# quadcopter-smith.net
KiCad netlist of a schematic drawn in EAGLE
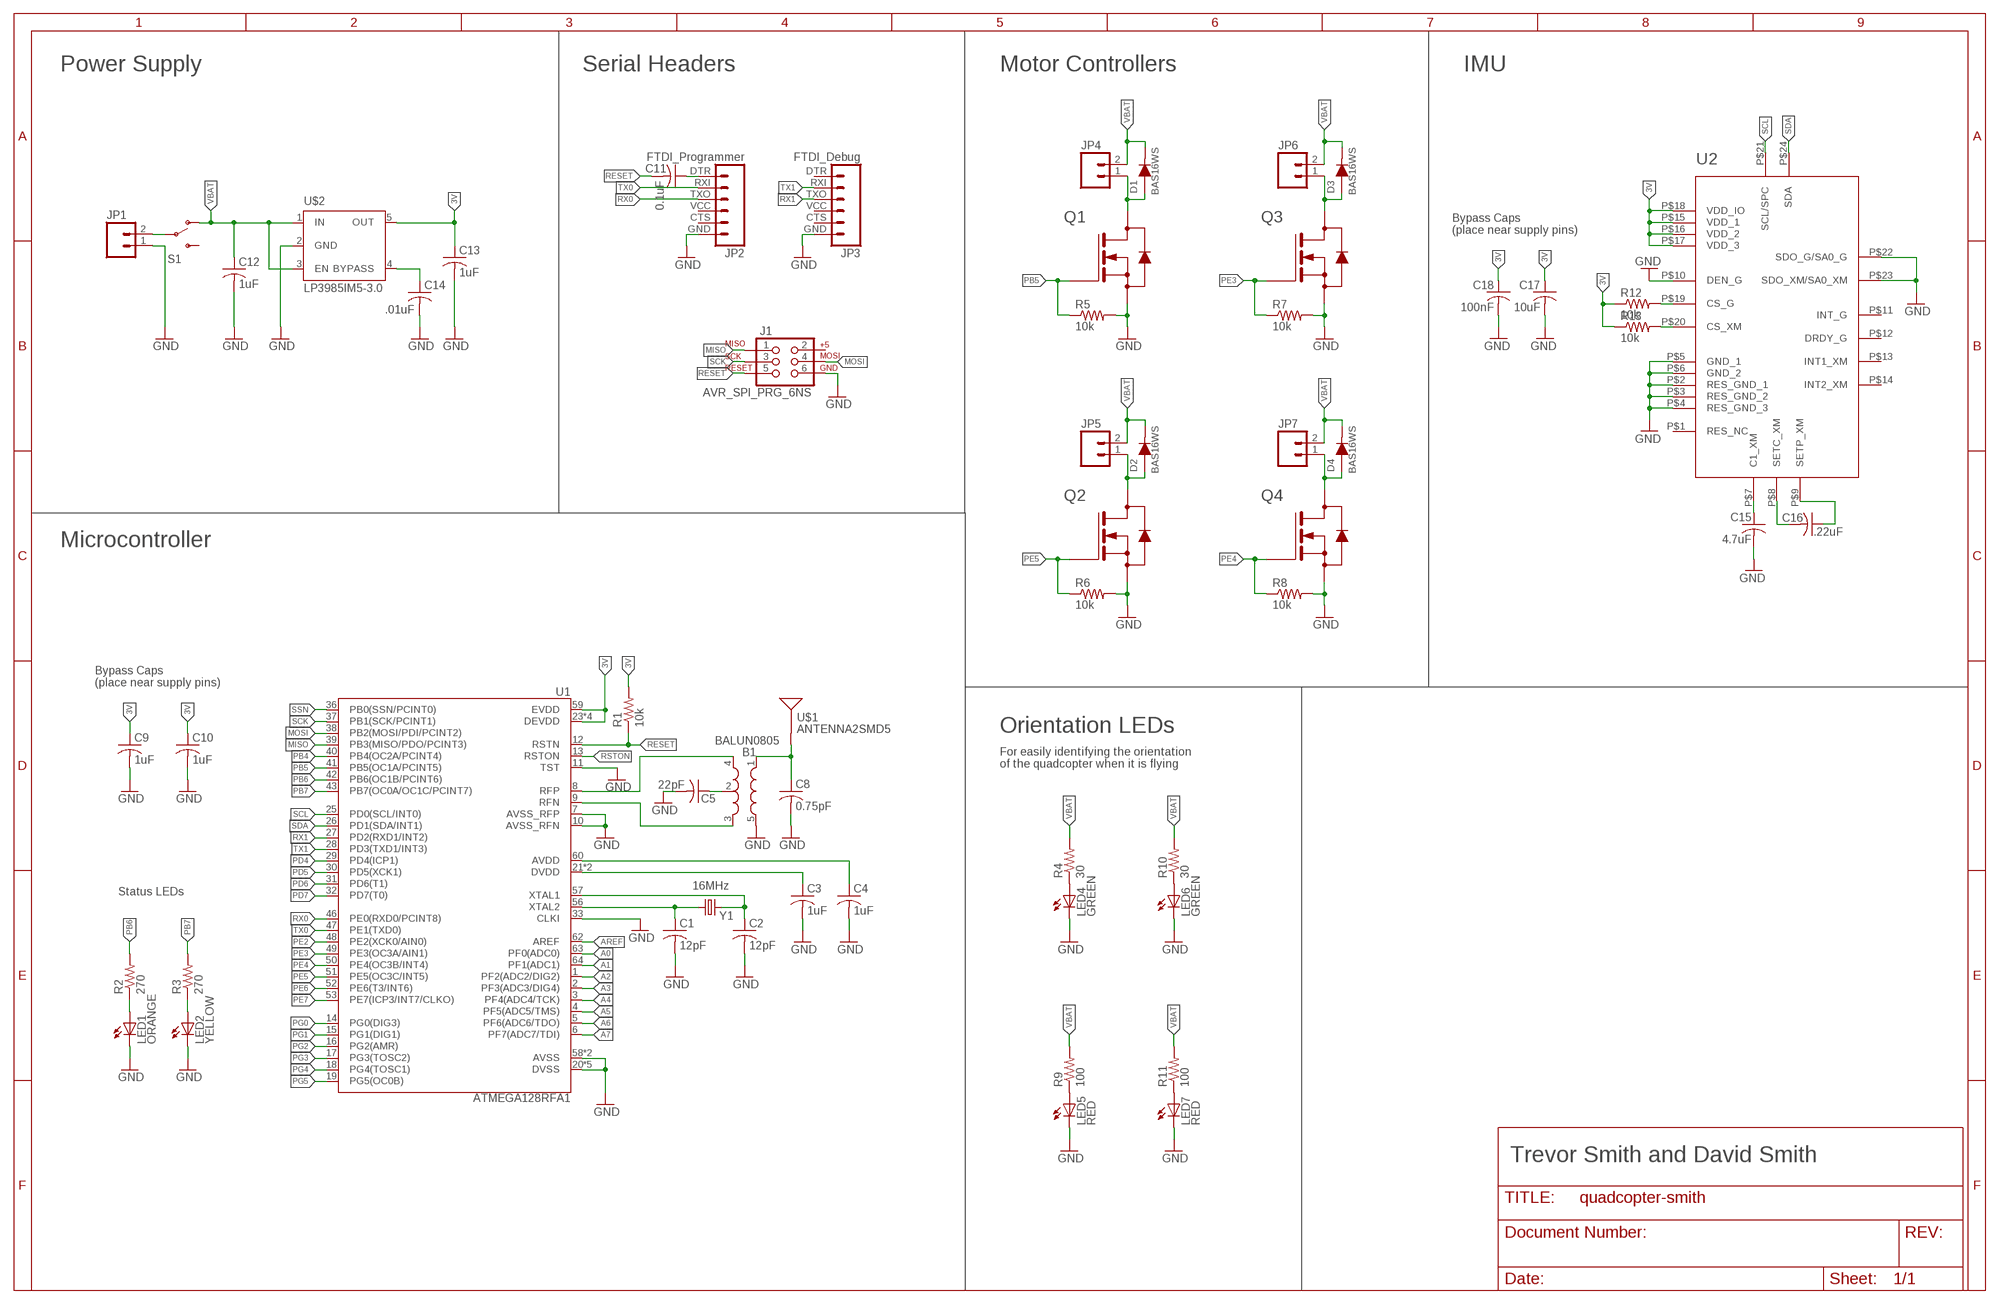
[diagram p0: schematic, sheet 1]

(export (version "E")
  (design (tool "Eeschema 10.0.6"))
  (components
    (comp (ref "B1")
      (value "BALUN0805")
      (footprint "eagle-import:BALUN")
      (libsource (lib "eagle-import") (part "BALUN0805"))
    )
    (comp (ref "C1")
      (value "12pF")
      (footprint "eagle-import:C0805")
      (libsource (lib "eagle-import") (part "C-USC0805"))
    )
    (comp (ref "C2")
      (value "12pF")
      (footprint "eagle-import:C0805")
      (libsource (lib "eagle-import") (part "C-USC0805"))
    )
    (comp (ref "C3")
      (value "1uF")
      (footprint "eagle-import:C0805")
      (libsource (lib "eagle-import") (part "C-USC0805"))
    )
    (comp (ref "C4")
      (value "1uF")
      (footprint "eagle-import:C0805")
      (libsource (lib "eagle-import") (part "C-USC0805"))
    )
    (comp (ref "C5")
      (value "22pF")
      (footprint "eagle-import:C0805")
      (libsource (lib "eagle-import") (part "C-USC0805"))
    )
    (comp (ref "C8")
      (value "0.75pF")
      (footprint "eagle-import:C0805")
      (libsource (lib "eagle-import") (part "C-USC0805"))
    )
    (comp (ref "C9")
      (value "1uF")
      (footprint "eagle-import:C0805")
      (libsource (lib "eagle-import") (part "C-USC0805"))
    )
    (comp (ref "C10")
      (value "1uF")
      (footprint "eagle-import:C0805")
      (libsource (lib "eagle-import") (part "C-USC0805"))
    )
    (comp (ref "C11")
      (value "0.1uF")
      (footprint "eagle-import:C0805")
      (libsource (lib "eagle-import") (part "C-USC0805"))
    )
    (comp (ref "C12")
      (value "1uF")
      (footprint "eagle-import:C0805")
      (libsource (lib "eagle-import") (part "C-USC0805"))
    )
    (comp (ref "C13")
      (value "1uF")
      (footprint "eagle-import:C0805")
      (libsource (lib "eagle-import") (part "C-USC0805"))
    )
    (comp (ref "C14")
      (value ".01uF")
      (footprint "eagle-import:C0805")
      (libsource (lib "eagle-import") (part "C-USC0805"))
    )
    (comp (ref "C15")
      (value "4.7uF")
      (footprint "eagle-import:C0805")
      (libsource (lib "eagle-import") (part "C-USC0805"))
    )
    (comp (ref "C16")
      (value ".22uF")
      (footprint "eagle-import:C0805")
      (libsource (lib "eagle-import") (part "C-USC0805"))
    )
    (comp (ref "C17")
      (value "10uF")
      (footprint "eagle-import:C0805")
      (libsource (lib "eagle-import") (part "C-USC0805"))
    )
    (comp (ref "C18")
      (value "100nF")
      (footprint "eagle-import:C0805")
      (libsource (lib "eagle-import") (part "C-USC0805"))
    )
    (comp (ref "D1")
      (value "BAS16WS")
      (footprint "eagle-import:SOD-323")
      (fields (field (name "CREATOR") "Trevor Smith"))
      (libsource (lib "eagle-import") (part "BAS16WS"))
    )
    (comp (ref "D2")
      (value "BAS16WS")
      (footprint "eagle-import:SOD-323")
      (fields (field (name "CREATOR") "Trevor Smith"))
      (libsource (lib "eagle-import") (part "BAS16WS"))
    )
    (comp (ref "D3")
      (value "BAS16WS")
      (footprint "eagle-import:SOD-323")
      (fields (field (name "CREATOR") "Trevor Smith"))
      (libsource (lib "eagle-import") (part "BAS16WS"))
    )
    (comp (ref "D4")
      (value "BAS16WS")
      (footprint "eagle-import:SOD-323")
      (fields (field (name "CREATOR") "Trevor Smith"))
      (libsource (lib "eagle-import") (part "BAS16WS"))
    )
    (comp (ref "J1")
      (value "AVR_SPI_PRG_6NS")
      (footprint "eagle-import:2X3-NS")
      (libsource (lib "eagle-import") (part "AVR_SPI_PRG_6NS"))
    )
    (comp (ref "JP1")
      (value "M02PTH")
      (footprint "eagle-import:1X02")
      (libsource (lib "eagle-import") (part "M02PTH"))
    )
    (comp (ref "JP2")
      (value "FTDI_Programmer")
      (footprint "eagle-import:FTDI_BASIC")
      (libsource (lib "eagle-import") (part "FTDI_BASICPTH"))
    )
    (comp (ref "JP3")
      (value "FTDI_Debug")
      (footprint "eagle-import:FTDI_BASIC")
      (libsource (lib "eagle-import") (part "FTDI_BASICPTH"))
    )
    (comp (ref "JP4")
      (value "M02PTH")
      (footprint "eagle-import:1X02")
      (libsource (lib "eagle-import") (part "M02PTH"))
    )
    (comp (ref "JP5")
      (value "M02PTH")
      (footprint "eagle-import:1X02")
      (libsource (lib "eagle-import") (part "M02PTH"))
    )
    (comp (ref "JP6")
      (value "M02PTH")
      (footprint "eagle-import:1X02")
      (libsource (lib "eagle-import") (part "M02PTH"))
    )
    (comp (ref "JP7")
      (value "M02PTH")
      (footprint "eagle-import:1X02")
      (libsource (lib "eagle-import") (part "M02PTH"))
    )
    (comp (ref "LED1")
      (value "ORANGE")
      (footprint "eagle-import:CHIP-LED0805")
      (libsource (lib "eagle-import") (part "LEDCHIP-LED0805"))
    )
    (comp (ref "LED2")
      (value "YELLOW")
      (footprint "eagle-import:CHIP-LED0805")
      (libsource (lib "eagle-import") (part "LEDCHIP-LED0805"))
    )
    (comp (ref "LED4")
      (value "GREEN")
      (footprint "eagle-import:CHIP-LED0805")
      (libsource (lib "eagle-import") (part "LEDCHIP-LED0805"))
    )
    (comp (ref "LED5")
      (value "RED")
      (footprint "eagle-import:CHIP-LED0805")
      (libsource (lib "eagle-import") (part "LEDCHIP-LED0805"))
    )
    (comp (ref "LED6")
      (value "GREEN")
      (footprint "eagle-import:CHIP-LED0805")
      (libsource (lib "eagle-import") (part "LEDCHIP-LED0805"))
    )
    (comp (ref "LED7")
      (value "RED")
      (footprint "eagle-import:CHIP-LED0805")
      (libsource (lib "eagle-import") (part "LEDCHIP-LED0805"))
    )
    (comp (ref "Q1")
      (value "SI2302CDS")
      (footprint "eagle-import:SOT-23")
      (fields (field (name "CREATOR") "Trevor Smith"))
      (libsource (lib "eagle-import") (part "SI2302CDS"))
    )
    (comp (ref "Q2")
      (value "SI2302CDS")
      (footprint "eagle-import:SOT-23")
      (fields (field (name "CREATOR") "Trevor Smith"))
      (libsource (lib "eagle-import") (part "SI2302CDS"))
    )
    (comp (ref "Q3")
      (value "SI2302CDS")
      (footprint "eagle-import:SOT-23")
      (fields (field (name "CREATOR") "Trevor Smith"))
      (libsource (lib "eagle-import") (part "SI2302CDS"))
    )
    (comp (ref "Q4")
      (value "SI2302CDS")
      (footprint "eagle-import:SOT-23")
      (fields (field (name "CREATOR") "Trevor Smith"))
      (libsource (lib "eagle-import") (part "SI2302CDS"))
    )
    (comp (ref "R1")
      (value "10k")
      (footprint "eagle-import:R0805")
      (libsource (lib "eagle-import") (part "R-US_R0805"))
    )
    (comp (ref "R2")
      (value "270")
      (footprint "eagle-import:R0805")
      (libsource (lib "eagle-import") (part "R-US_R0805"))
    )
    (comp (ref "R3")
      (value "270")
      (footprint "eagle-import:R0805")
      (libsource (lib "eagle-import") (part "R-US_R0805"))
    )
    (comp (ref "R4")
      (value "30")
      (footprint "eagle-import:R0805")
      (libsource (lib "eagle-import") (part "R-US_R0805"))
    )
    (comp (ref "R5")
      (value "10k")
      (footprint "eagle-import:R0805")
      (libsource (lib "eagle-import") (part "R-US_R0805"))
    )
    (comp (ref "R6")
      (value "10k")
      (footprint "eagle-import:R0805")
      (libsource (lib "eagle-import") (part "R-US_R0805"))
    )
    (comp (ref "R7")
      (value "10k")
      (footprint "eagle-import:R0805")
      (libsource (lib "eagle-import") (part "R-US_R0805"))
    )
    (comp (ref "R8")
      (value "10k")
      (footprint "eagle-import:R0805")
      (libsource (lib "eagle-import") (part "R-US_R0805"))
    )
    (comp (ref "R9")
      (value "100")
      (footprint "eagle-import:R0805")
      (libsource (lib "eagle-import") (part "R-US_R0805"))
    )
    (comp (ref "R10")
      (value "30")
      (footprint "eagle-import:R0805")
      (libsource (lib "eagle-import") (part "R-US_R0805"))
    )
    (comp (ref "R11")
      (value "100")
      (footprint "eagle-import:R0805")
      (libsource (lib "eagle-import") (part "R-US_R0805"))
    )
    (comp (ref "R12")
      (value "10k")
      (footprint "eagle-import:R0805")
      (libsource (lib "eagle-import") (part "R-US_R0805"))
    )
    (comp (ref "R13")
      (value "10k")
      (footprint "eagle-import:R0805")
      (libsource (lib "eagle-import") (part "R-US_R0805"))
    )
    (comp (ref "S1")
      (value "SWITCH-SPDTPTH")
      (footprint "eagle-import:SWITCH-SPDT")
      (libsource (lib "eagle-import") (part "SWITCH-SPDTPTH"))
    )
    (comp (ref "U$1")
      (value "ANTENNA2SMD5")
      (footprint "eagle-import:ANTENNA-CHIP5")
      (libsource (lib "eagle-import") (part "ANTENNA2SMD5"))
    )
    (comp (ref "U$2")
      (value "LP3985IM5-3.0")
      (footprint "eagle-import:SOT23-DBV")
      (libsource (lib "eagle-import") (part "LP3985IM5-3.0"))
    )
    (comp (ref "U1")
      (value "ATMEGA128RFA1")
      (footprint "eagle-import:QFN-64")
      (libsource (lib "eagle-import") (part "ATMEGA128RFA1"))
    )
    (comp (ref "U2")
      (value "LSM9DS0-LGA24")
      (footprint "eagle-import:LGA-24")
      (fields (field (name "CREATOR") "Trevor Smith"))
      (libsource (lib "eagle-import") (part "LSM9DS0-LGA24"))
    )
    (comp (ref "Y1")
      (value "16MHz")
      (footprint "eagle-import:CRYSTAL-SMD-5X3")
      (libsource (lib "eagle-import") (part "CRYSTAL5X3"))
    )
  )
  (nets
    (net (code "1") (name "3V") (class "Default")
      (node (ref "C10") (pin "1") (pinfunction "1_1") (pintype "passive"))
      (node (ref "C13") (pin "1") (pinfunction "1_1") (pintype "passive"))
      (node (ref "C17") (pin "1") (pinfunction "1_1") (pintype "passive"))
      (node (ref "C18") (pin "1") (pinfunction "1_1") (pintype "passive"))
      (node (ref "C9") (pin "1") (pinfunction "1_1") (pintype "passive"))
      (node (ref "R1") (pin "2") (pinfunction "2_2") (pintype "passive"))
      (node (ref "R12") (pin "1") (pinfunction "1_1") (pintype "passive"))
      (node (ref "R13") (pin "1") (pinfunction "1_1") (pintype "passive"))
      (node (ref "U$2") (pin "5") (pinfunction "OUT_5") (pintype "passive"))
      (node (ref "U1") (pin "23") (pinfunction "DEVDD_23") (pintype "bidirectional"))
      (node (ref "U1") (pin "34") (pinfunction "DEVDD_34") (pintype "bidirectional"))
      (node (ref "U1") (pin "44") (pinfunction "DEVDD_44") (pintype "bidirectional"))
      (node (ref "U1") (pin "54") (pinfunction "DEVDD_54") (pintype "bidirectional"))
      (node (ref "U1") (pin "59") (pinfunction "EVDD_59") (pintype "bidirectional"))
      (node (ref "U2") (pin "P$15") (pinfunction "VDD_1_P$15") (pintype "power_in"))
      (node (ref "U2") (pin "P$16") (pinfunction "VDD_2_P$16") (pintype "power_in"))
      (node (ref "U2") (pin "P$17") (pinfunction "VDD_3_P$17") (pintype "power_in"))
      (node (ref "U2") (pin "P$18") (pinfunction "VDD_IO_P$18") (pintype "power_in"))
    )
    (net (code "2") (name "A0") (class "Default")
      (node (ref "U1") (pin "63") (pinfunction "PF0(ADC0)_63") (pintype "bidirectional"))
    )
    (net (code "3") (name "A1") (class "Default")
      (node (ref "U1") (pin "64") (pinfunction "PF1(ADC1)_64") (pintype "bidirectional"))
    )
    (net (code "4") (name "A2") (class "Default")
      (node (ref "U1") (pin "1") (pinfunction "PF2(ADC2/DIG2)_1") (pintype "bidirectional"))
    )
    (net (code "5") (name "A3") (class "Default")
      (node (ref "U1") (pin "2") (pinfunction "PF3(ADC3/DIG4)_2") (pintype "bidirectional"))
    )
    (net (code "6") (name "A4") (class "Default")
      (node (ref "U1") (pin "3") (pinfunction "PF4(ADC4/TCK)_3") (pintype "bidirectional"))
    )
    (net (code "7") (name "A5") (class "Default")
      (node (ref "U1") (pin "4") (pinfunction "PF5(ADC5/TMS)_4") (pintype "bidirectional"))
    )
    (net (code "8") (name "A6") (class "Default")
      (node (ref "U1") (pin "5") (pinfunction "PF6(ADC6/TDO)_5") (pintype "bidirectional"))
    )
    (net (code "9") (name "A7") (class "Default")
      (node (ref "U1") (pin "6") (pinfunction "PF7(ADC7/TDI)_6") (pintype "bidirectional"))
    )
    (net (code "10") (name "AREF") (class "Default")
      (node (ref "U1") (pin "62") (pinfunction "AREF_62") (pintype "bidirectional"))
    )
    (net (code "11") (name "GND") (class "Default")
      (node (ref "B1") (pin "5") (pinfunction "GND_5") (pintype "bidirectional"))
      (node (ref "C1") (pin "2") (pinfunction "2_2") (pintype "passive"))
      (node (ref "C10") (pin "2") (pinfunction "2_2") (pintype "passive"))
      (node (ref "C12") (pin "2") (pinfunction "2_2") (pintype "passive"))
      (node (ref "C13") (pin "2") (pinfunction "2_2") (pintype "passive"))
      (node (ref "C14") (pin "2") (pinfunction "2_2") (pintype "passive"))
      (node (ref "C15") (pin "2") (pinfunction "2_2") (pintype "passive"))
      (node (ref "C17") (pin "2") (pinfunction "2_2") (pintype "passive"))
      (node (ref "C18") (pin "2") (pinfunction "2_2") (pintype "passive"))
      (node (ref "C2") (pin "2") (pinfunction "2_2") (pintype "passive"))
      (node (ref "C3") (pin "2") (pinfunction "2_2") (pintype "passive"))
      (node (ref "C4") (pin "2") (pinfunction "2_2") (pintype "passive"))
      (node (ref "C5") (pin "2") (pinfunction "2_2") (pintype "passive"))
      (node (ref "C8") (pin "2") (pinfunction "2_2") (pintype "passive"))
      (node (ref "C9") (pin "2") (pinfunction "2_2") (pintype "passive"))
      (node (ref "J1") (pin "6") (pinfunction "6_6") (pintype "passive"))
      (node (ref "JP1") (pin "1") (pinfunction "1_1") (pintype "passive"))
      (node (ref "JP2") (pin "GND") (pinfunction "6_GND") (pintype "passive"))
      (node (ref "JP3") (pin "GND") (pinfunction "6_GND") (pintype "passive"))
      (node (ref "LED1") (pin "C") (pinfunction "C_C") (pintype "passive"))
      (node (ref "LED2") (pin "C") (pinfunction "C_C") (pintype "passive"))
      (node (ref "LED4") (pin "C") (pinfunction "C_C") (pintype "passive"))
      (node (ref "LED5") (pin "C") (pinfunction "C_C") (pintype "passive"))
      (node (ref "LED6") (pin "C") (pinfunction "C_C") (pintype "passive"))
      (node (ref "LED7") (pin "C") (pinfunction "C_C") (pintype "passive"))
      (node (ref "Q1") (pin "P$2") (pinfunction "S_P$2") (pintype "bidirectional"))
      (node (ref "Q2") (pin "P$2") (pinfunction "S_P$2") (pintype "bidirectional"))
      (node (ref "Q3") (pin "P$2") (pinfunction "S_P$2") (pintype "bidirectional"))
      (node (ref "Q4") (pin "P$2") (pinfunction "S_P$2") (pintype "bidirectional"))
      (node (ref "R5") (pin "2") (pinfunction "2_2") (pintype "passive"))
      (node (ref "R6") (pin "2") (pinfunction "2_2") (pintype "passive"))
      (node (ref "R7") (pin "2") (pinfunction "2_2") (pintype "passive"))
      (node (ref "R8") (pin "2") (pinfunction "2_2") (pintype "passive"))
      (node (ref "U$2") (pin "2") (pinfunction "GND_2") (pintype "input"))
      (node (ref "U1") (pin "10") (pinfunction "AVSS_RFN_10") (pintype "bidirectional"))
      (node (ref "U1") (pin "11") (pinfunction "TST_11") (pintype "bidirectional"))
      (node (ref "U1") (pin "20") (pinfunction "DVSS_20") (pintype "bidirectional"))
      (node (ref "U1") (pin "24") (pinfunction "DVSS_24") (pintype "bidirectional"))
      (node (ref "U1") (pin "33") (pinfunction "CLKI_33") (pintype "bidirectional"))
      (node (ref "U1") (pin "35") (pinfunction "DVSS_35") (pintype "bidirectional"))
      (node (ref "U1") (pin "45") (pinfunction "DVSS_45") (pintype "bidirectional"))
      (node (ref "U1") (pin "55") (pinfunction "DVSS_55") (pintype "bidirectional"))
      (node (ref "U1") (pin "58") (pinfunction "AVSS_58") (pintype "bidirectional"))
      (node (ref "U1") (pin "61") (pinfunction "AVSS_61") (pintype "bidirectional"))
      (node (ref "U1") (pin "7") (pinfunction "AVSS_RFP_7") (pintype "bidirectional"))
      (node (ref "U2") (pin "P$10") (pinfunction "DEN_G_P$10") (pintype "input"))
      (node (ref "U2") (pin "P$2") (pinfunction "RES_GND_1_P$2") (pintype "power_in"))
      (node (ref "U2") (pin "P$22") (pinfunction "SDO_G/SA0_G_P$22") (pintype "bidirectional"))
      (node (ref "U2") (pin "P$23") (pinfunction "SDO_XM/SA0_XM_P$23") (pintype "bidirectional"))
      (node (ref "U2") (pin "P$3") (pinfunction "RES_GND_2_P$3") (pintype "power_in"))
      (node (ref "U2") (pin "P$4") (pinfunction "RES_GND_3_P$4") (pintype "power_in"))
      (node (ref "U2") (pin "P$5") (pinfunction "GND_1_P$5") (pintype "power_in"))
      (node (ref "U2") (pin "P$6") (pinfunction "GND_2_P$6") (pintype "power_in"))
    )
    (net (code "12") (name "MISO") (class "Default")
      (node (ref "J1") (pin "1") (pinfunction "1_1") (pintype "passive"))
      (node (ref "U1") (pin "39") (pinfunction "PB3(MISO/PDO/PCINT3)_39") (pintype "bidirectional"))
    )
    (net (code "13") (name "MOSI") (class "Default")
      (node (ref "J1") (pin "4") (pinfunction "4_4") (pintype "passive"))
      (node (ref "U1") (pin "38") (pinfunction "PB2(MOSI/PDI/PCINT2)_38") (pintype "bidirectional"))
    )
    (net (code "14") (name "Net-(B1-GND-Pad2)") (class "Default")
      (node (ref "B1") (pin "2") (pinfunction "GND_2") (pintype "bidirectional"))
      (node (ref "C5") (pin "1") (pinfunction "1_1") (pintype "passive"))
    )
    (net (code "15") (name "Net-(B1-IN)") (class "Default")
      (node (ref "B1") (pin "1") (pinfunction "IN_1") (pintype "bidirectional"))
      (node (ref "C8") (pin "1") (pinfunction "1_1") (pintype "passive"))
      (node (ref "U$1") (pin "FEED") (pinfunction "SIGNAL_FEED") (pintype "bidirectional"))
    )
    (net (code "16") (name "Net-(B1-OUT1)") (class "Default")
      (node (ref "B1") (pin "4") (pinfunction "OUT1_4") (pintype "bidirectional"))
      (node (ref "U1") (pin "8") (pinfunction "RFP_8") (pintype "bidirectional"))
    )
    (net (code "17") (name "Net-(B1-OUT2)") (class "Default")
      (node (ref "B1") (pin "3") (pinfunction "OUT2_3") (pintype "bidirectional"))
      (node (ref "U1") (pin "9") (pinfunction "RFN_9") (pintype "bidirectional"))
    )
    (net (code "18") (name "Net-(C3-Pad1)") (class "Default")
      (node (ref "C3") (pin "1") (pinfunction "1_1") (pintype "passive"))
      (node (ref "U1") (pin "21") (pinfunction "DVDD_21") (pintype "bidirectional"))
      (node (ref "U1") (pin "22") (pinfunction "DVDD_22") (pintype "bidirectional"))
    )
    (net (code "19") (name "Net-(JP2-1)") (class "Default")
      (node (ref "C11") (pin "1") (pinfunction "1_1") (pintype "passive"))
      (node (ref "JP2") (pin "DTR") (pinfunction "1_DTR") (pintype "passive"))
    )
    (net (code "20") (name "Net-(LED1-PadA)") (class "Default")
      (node (ref "LED1") (pin "A") (pinfunction "A_A") (pintype "passive"))
      (node (ref "R2") (pin "1") (pinfunction "1_1") (pintype "passive"))
    )
    (net (code "21") (name "Net-(LED2-PadA)") (class "Default")
      (node (ref "LED2") (pin "A") (pinfunction "A_A") (pintype "passive"))
      (node (ref "R3") (pin "1") (pinfunction "1_1") (pintype "passive"))
    )
    (net (code "22") (name "Net-(LED4-PadA)") (class "Default")
      (node (ref "LED4") (pin "A") (pinfunction "A_A") (pintype "passive"))
      (node (ref "R4") (pin "1") (pinfunction "1_1") (pintype "passive"))
    )
    (net (code "23") (name "Net-(LED5-PadA)") (class "Default")
      (node (ref "LED5") (pin "A") (pinfunction "A_A") (pintype "passive"))
      (node (ref "R9") (pin "1") (pinfunction "1_1") (pintype "passive"))
    )
    (net (code "24") (name "Net-(LED6-PadA)") (class "Default")
      (node (ref "LED6") (pin "A") (pinfunction "A_A") (pintype "passive"))
      (node (ref "R10") (pin "1") (pinfunction "1_1") (pintype "passive"))
    )
    (net (code "25") (name "Net-(LED7-PadA)") (class "Default")
      (node (ref "LED7") (pin "A") (pinfunction "A_A") (pintype "passive"))
      (node (ref "R11") (pin "1") (pinfunction "1_1") (pintype "passive"))
    )
    (net (code "26") (name "Net-(Q1-D)") (class "Default")
      (node (ref "D1") (pin "P$1") (pinfunction "P$1_P$1") (pintype "passive"))
      (node (ref "JP4") (pin "1") (pinfunction "1_1") (pintype "passive"))
      (node (ref "Q1") (pin "P$3") (pinfunction "D_P$3") (pintype "bidirectional"))
    )
    (net (code "27") (name "Net-(Q2-D)") (class "Default")
      (node (ref "D2") (pin "P$1") (pinfunction "P$1_P$1") (pintype "passive"))
      (node (ref "JP5") (pin "1") (pinfunction "1_1") (pintype "passive"))
      (node (ref "Q2") (pin "P$3") (pinfunction "D_P$3") (pintype "bidirectional"))
    )
    (net (code "28") (name "Net-(Q3-D)") (class "Default")
      (node (ref "D3") (pin "P$1") (pinfunction "P$1_P$1") (pintype "passive"))
      (node (ref "JP6") (pin "1") (pinfunction "1_1") (pintype "passive"))
      (node (ref "Q3") (pin "P$3") (pinfunction "D_P$3") (pintype "bidirectional"))
    )
    (net (code "29") (name "Net-(Q4-D)") (class "Default")
      (node (ref "D4") (pin "P$1") (pinfunction "P$1_P$1") (pintype "passive"))
      (node (ref "JP7") (pin "1") (pinfunction "1_1") (pintype "passive"))
      (node (ref "Q4") (pin "P$3") (pinfunction "D_P$3") (pintype "bidirectional"))
    )
    (net (code "30") (name "Net-(S1-P)") (class "Default")
      (node (ref "JP1") (pin "2") (pinfunction "2_2") (pintype "passive"))
      (node (ref "S1") (pin "2") (pinfunction "P_2") (pintype "passive"))
    )
    (net (code "31") (name "Net-(U$2-BYPASS)") (class "Default")
      (node (ref "C14") (pin "1") (pinfunction "1_1") (pintype "passive"))
      (node (ref "U$2") (pin "4") (pinfunction "BYPASS_4") (pintype "passive"))
    )
    (net (code "32") (name "Net-(U1-AVDD)") (class "Default")
      (node (ref "C4") (pin "1") (pinfunction "1_1") (pintype "passive"))
      (node (ref "U1") (pin "60") (pinfunction "AVDD_60") (pintype "bidirectional"))
    )
    (net (code "33") (name "Net-(U1-XTAL1)") (class "Default")
      (node (ref "C2") (pin "1") (pinfunction "1_1") (pintype "passive"))
      (node (ref "U1") (pin "57") (pinfunction "XTAL1_57") (pintype "bidirectional"))
      (node (ref "Y1") (pin "3") (pinfunction "2_3") (pintype "passive"))
    )
    (net (code "34") (name "Net-(U1-XTAL2)") (class "Default")
      (node (ref "C1") (pin "1") (pinfunction "1_1") (pintype "passive"))
      (node (ref "U1") (pin "56") (pinfunction "XTAL2_56") (pintype "bidirectional"))
      (node (ref "Y1") (pin "1") (pinfunction "1_1") (pintype "passive"))
    )
    (net (code "35") (name "Net-(U2-C1_XM)") (class "Default")
      (node (ref "C15") (pin "1") (pinfunction "1_1") (pintype "passive"))
      (node (ref "U2") (pin "P$7") (pinfunction "C1_XM_P$7") (pintype "passive"))
    )
    (net (code "36") (name "Net-(U2-CS_G)") (class "Default")
      (node (ref "R12") (pin "2") (pinfunction "2_2") (pintype "passive"))
      (node (ref "U2") (pin "P$19") (pinfunction "CS_G_P$19") (pintype "input"))
    )
    (net (code "37") (name "Net-(U2-CS_XM)") (class "Default")
      (node (ref "R13") (pin "2") (pinfunction "2_2") (pintype "passive"))
      (node (ref "U2") (pin "P$20") (pinfunction "CS_XM_P$20") (pintype "input"))
    )
    (net (code "38") (name "Net-(U2-SETC_XM)") (class "Default")
      (node (ref "C16") (pin "2") (pinfunction "2_2") (pintype "passive"))
      (node (ref "U2") (pin "P$8") (pinfunction "SETC_XM_P$8") (pintype "passive"))
    )
    (net (code "39") (name "Net-(U2-SETP_XM)") (class "Default")
      (node (ref "C16") (pin "1") (pinfunction "1_1") (pintype "passive"))
      (node (ref "U2") (pin "P$9") (pinfunction "SETP_XM_P$9") (pintype "passive"))
    )
    (net (code "40") (name "PB4") (class "Default")
      (node (ref "U1") (pin "40") (pinfunction "PB4(OC2A/PCINT4)_40") (pintype "bidirectional"))
    )
    (net (code "41") (name "PB5") (class "Default")
      (node (ref "Q1") (pin "P$1") (pinfunction "G_P$1") (pintype "bidirectional"))
      (node (ref "R5") (pin "1") (pinfunction "1_1") (pintype "passive"))
      (node (ref "U1") (pin "41") (pinfunction "PB5(OC1A/PCINT5)_41") (pintype "bidirectional"))
    )
    (net (code "42") (name "PB6") (class "Default")
      (node (ref "R2") (pin "2") (pinfunction "2_2") (pintype "passive"))
      (node (ref "U1") (pin "42") (pinfunction "PB6(OC1B/PCINT6)_42") (pintype "bidirectional"))
    )
    (net (code "43") (name "PB7") (class "Default")
      (node (ref "R3") (pin "2") (pinfunction "2_2") (pintype "passive"))
      (node (ref "U1") (pin "43") (pinfunction "PB7(OC0A/OC1C/PCINT7)_43") (pintype "bidirectional"))
    )
    (net (code "44") (name "PD4") (class "Default")
      (node (ref "U1") (pin "29") (pinfunction "PD4(ICP1)_29") (pintype "bidirectional"))
    )
    (net (code "45") (name "PD5") (class "Default")
      (node (ref "U1") (pin "30") (pinfunction "PD5(XCK1)_30") (pintype "bidirectional"))
    )
    (net (code "46") (name "PD6") (class "Default")
      (node (ref "U1") (pin "31") (pinfunction "PD6(T1)_31") (pintype "bidirectional"))
    )
    (net (code "47") (name "PD7") (class "Default")
      (node (ref "U1") (pin "32") (pinfunction "PD7(T0)_32") (pintype "bidirectional"))
    )
    (net (code "48") (name "PE2") (class "Default")
      (node (ref "U1") (pin "48") (pinfunction "PE2(XCK0/AIN0)_48") (pintype "bidirectional"))
    )
    (net (code "49") (name "PE3") (class "Default")
      (node (ref "Q3") (pin "P$1") (pinfunction "G_P$1") (pintype "bidirectional"))
      (node (ref "R7") (pin "1") (pinfunction "1_1") (pintype "passive"))
      (node (ref "U1") (pin "49") (pinfunction "PE3(OC3A/AIN1)_49") (pintype "bidirectional"))
    )
    (net (code "50") (name "PE4") (class "Default")
      (node (ref "Q4") (pin "P$1") (pinfunction "G_P$1") (pintype "bidirectional"))
      (node (ref "R8") (pin "1") (pinfunction "1_1") (pintype "passive"))
      (node (ref "U1") (pin "50") (pinfunction "PE4(OC3B/INT4)_50") (pintype "bidirectional"))
    )
    (net (code "51") (name "PE5") (class "Default")
      (node (ref "Q2") (pin "P$1") (pinfunction "G_P$1") (pintype "bidirectional"))
      (node (ref "R6") (pin "1") (pinfunction "1_1") (pintype "passive"))
      (node (ref "U1") (pin "51") (pinfunction "PE5(OC3C/INT5)_51") (pintype "bidirectional"))
    )
    (net (code "52") (name "PE6") (class "Default")
      (node (ref "U1") (pin "52") (pinfunction "PE6(T3/INT6)_52") (pintype "bidirectional"))
    )
    (net (code "53") (name "PE7") (class "Default")
      (node (ref "U1") (pin "53") (pinfunction "PE7(ICP3/INT7/CLKO)_53") (pintype "bidirectional"))
    )
    (net (code "54") (name "PG0") (class "Default")
      (node (ref "U1") (pin "14") (pinfunction "PG0(DIG3)_14") (pintype "bidirectional"))
    )
    (net (code "55") (name "PG1") (class "Default")
      (node (ref "U1") (pin "15") (pinfunction "PG1(DIG1)_15") (pintype "bidirectional"))
    )
    (net (code "56") (name "PG2") (class "Default")
      (node (ref "U1") (pin "16") (pinfunction "PG2(AMR)_16") (pintype "bidirectional"))
    )
    (net (code "57") (name "PG3") (class "Default")
      (node (ref "U1") (pin "17") (pinfunction "PG3(TOSC2)_17") (pintype "bidirectional"))
    )
    (net (code "58") (name "PG4") (class "Default")
      (node (ref "U1") (pin "18") (pinfunction "PG4(TOSC1)_18") (pintype "bidirectional"))
    )
    (net (code "59") (name "PG5") (class "Default")
      (node (ref "U1") (pin "19") (pinfunction "PG5(OC0B)_19") (pintype "bidirectional"))
    )
    (net (code "60") (name "RESET") (class "Default")
      (node (ref "C11") (pin "2") (pinfunction "2_2") (pintype "passive"))
      (node (ref "J1") (pin "5") (pinfunction "5_5") (pintype "passive"))
      (node (ref "R1") (pin "1") (pinfunction "1_1") (pintype "passive"))
      (node (ref "U1") (pin "12") (pinfunction "RSTN_12") (pintype "bidirectional"))
    )
    (net (code "61") (name "RSTON") (class "Default")
      (node (ref "U1") (pin "13") (pinfunction "RSTON_13") (pintype "bidirectional"))
    )
    (net (code "62") (name "RX0") (class "Default")
      (node (ref "JP2") (pin "TXO") (pinfunction "3_TXO") (pintype "passive"))
      (node (ref "U1") (pin "46") (pinfunction "PE0(RXD0/PCINT8)_46") (pintype "bidirectional"))
    )
    (net (code "63") (name "RX1") (class "Default")
      (node (ref "JP3") (pin "TXO") (pinfunction "3_TXO") (pintype "passive"))
      (node (ref "U1") (pin "27") (pinfunction "PD2(RXD1/INT2)_27") (pintype "bidirectional"))
    )
    (net (code "64") (name "SCK") (class "Default")
      (node (ref "J1") (pin "3") (pinfunction "3_3") (pintype "passive"))
      (node (ref "U1") (pin "37") (pinfunction "PB1(SCK/PCINT1)_37") (pintype "bidirectional"))
    )
    (net (code "65") (name "SCL") (class "Default")
      (node (ref "U1") (pin "25") (pinfunction "PD0(SCL/INT0)_25") (pintype "bidirectional"))
      (node (ref "U2") (pin "P$21") (pinfunction "SCL/SPC_P$21") (pintype "bidirectional"))
    )
    (net (code "66") (name "SDA") (class "Default")
      (node (ref "U1") (pin "26") (pinfunction "PD1(SDA/INT1)_26") (pintype "bidirectional"))
      (node (ref "U2") (pin "P$24") (pinfunction "SDA_P$24") (pintype "bidirectional"))
    )
    (net (code "67") (name "SSN") (class "Default")
      (node (ref "U1") (pin "36") (pinfunction "PB0(SSN/PCINT0)_36") (pintype "bidirectional"))
    )
    (net (code "68") (name "TX0") (class "Default")
      (node (ref "JP2") (pin "RXI") (pinfunction "2_RXI") (pintype "passive"))
      (node (ref "U1") (pin "47") (pinfunction "PE1(TXD0)_47") (pintype "bidirectional"))
    )
    (net (code "69") (name "TX1") (class "Default")
      (node (ref "JP3") (pin "RXI") (pinfunction "2_RXI") (pintype "passive"))
      (node (ref "U1") (pin "28") (pinfunction "PD3(TXD1/INT3)_28") (pintype "bidirectional"))
    )
    (net (code "70") (name "VBAT") (class "Default")
      (node (ref "C12") (pin "1") (pinfunction "1_1") (pintype "passive"))
      (node (ref "D1") (pin "P$2") (pinfunction "P$2_P$2") (pintype "passive"))
      (node (ref "D2") (pin "P$2") (pinfunction "P$2_P$2") (pintype "passive"))
      (node (ref "D3") (pin "P$2") (pinfunction "P$2_P$2") (pintype "passive"))
      (node (ref "D4") (pin "P$2") (pinfunction "P$2_P$2") (pintype "passive"))
      (node (ref "JP4") (pin "2") (pinfunction "2_2") (pintype "passive"))
      (node (ref "JP5") (pin "2") (pinfunction "2_2") (pintype "passive"))
      (node (ref "JP6") (pin "2") (pinfunction "2_2") (pintype "passive"))
      (node (ref "JP7") (pin "2") (pinfunction "2_2") (pintype "passive"))
      (node (ref "R10") (pin "2") (pinfunction "2_2") (pintype "passive"))
      (node (ref "R11") (pin "2") (pinfunction "2_2") (pintype "passive"))
      (node (ref "R4") (pin "2") (pinfunction "2_2") (pintype "passive"))
      (node (ref "R9") (pin "2") (pinfunction "2_2") (pintype "passive"))
      (node (ref "S1") (pin "1") (pinfunction "O_1") (pintype "passive"))
      (node (ref "U$2") (pin "1") (pinfunction "IN_1") (pintype "input"))
      (node (ref "U$2") (pin "3") (pinfunction "EN_3") (pintype "input"))
    )
    (net (code "71") (name "unconnected-(J1-Pad2)") (class "Default")
      (node (ref "J1") (pin "2") (pinfunction "2_2") (pintype "passive"))
    )
    (net (code "72") (name "unconnected-(JP2-4-PadVCC)") (class "Default")
      (node (ref "JP2") (pin "VCC") (pinfunction "4_VCC") (pintype "passive"))
    )
    (net (code "73") (name "unconnected-(JP2-5-PadCTS)") (class "Default")
      (node (ref "JP2") (pin "CTS") (pinfunction "5_CTS") (pintype "passive"))
    )
    (net (code "74") (name "unconnected-(JP3-1-PadDTR)") (class "Default")
      (node (ref "JP3") (pin "DTR") (pinfunction "1_DTR") (pintype "passive"))
    )
    (net (code "75") (name "unconnected-(JP3-4-PadVCC)") (class "Default")
      (node (ref "JP3") (pin "VCC") (pinfunction "4_VCC") (pintype "passive"))
    )
    (net (code "76") (name "unconnected-(JP3-5-PadCTS)") (class "Default")
      (node (ref "JP3") (pin "CTS") (pinfunction "5_CTS") (pintype "passive"))
    )
    (net (code "77") (name "unconnected-(S1-S-Pad3)") (class "Default")
      (node (ref "S1") (pin "3") (pinfunction "S_3") (pintype "passive"))
    )
    (net (code "78") (name "unconnected-(U2-DRDY_G-PadP$12)") (class "Default")
      (node (ref "U2") (pin "P$12") (pinfunction "DRDY_G_P$12") (pintype "output"))
    )
    (net (code "79") (name "unconnected-(U2-INT1_XM-PadP$13)") (class "Default")
      (node (ref "U2") (pin "P$13") (pinfunction "INT1_XM_P$13") (pintype "output"))
    )
    (net (code "80") (name "unconnected-(U2-INT2_XM-PadP$14)") (class "Default")
      (node (ref "U2") (pin "P$14") (pinfunction "INT2_XM_P$14") (pintype "output"))
    )
    (net (code "81") (name "unconnected-(U2-INT_G-PadP$11)") (class "Default")
      (node (ref "U2") (pin "P$11") (pinfunction "INT_G_P$11") (pintype "output"))
    )
    (net (code "82") (name "unconnected-(U2-RES_NC-PadP$1)") (class "Default")
      (node (ref "U2") (pin "P$1") (pinfunction "RES_NC_P$1") (pintype "no_connect"))
    )
  )
)
